# FrontEnd-signals.net
KiCad netlist of a schematic drawn in Altium Designer
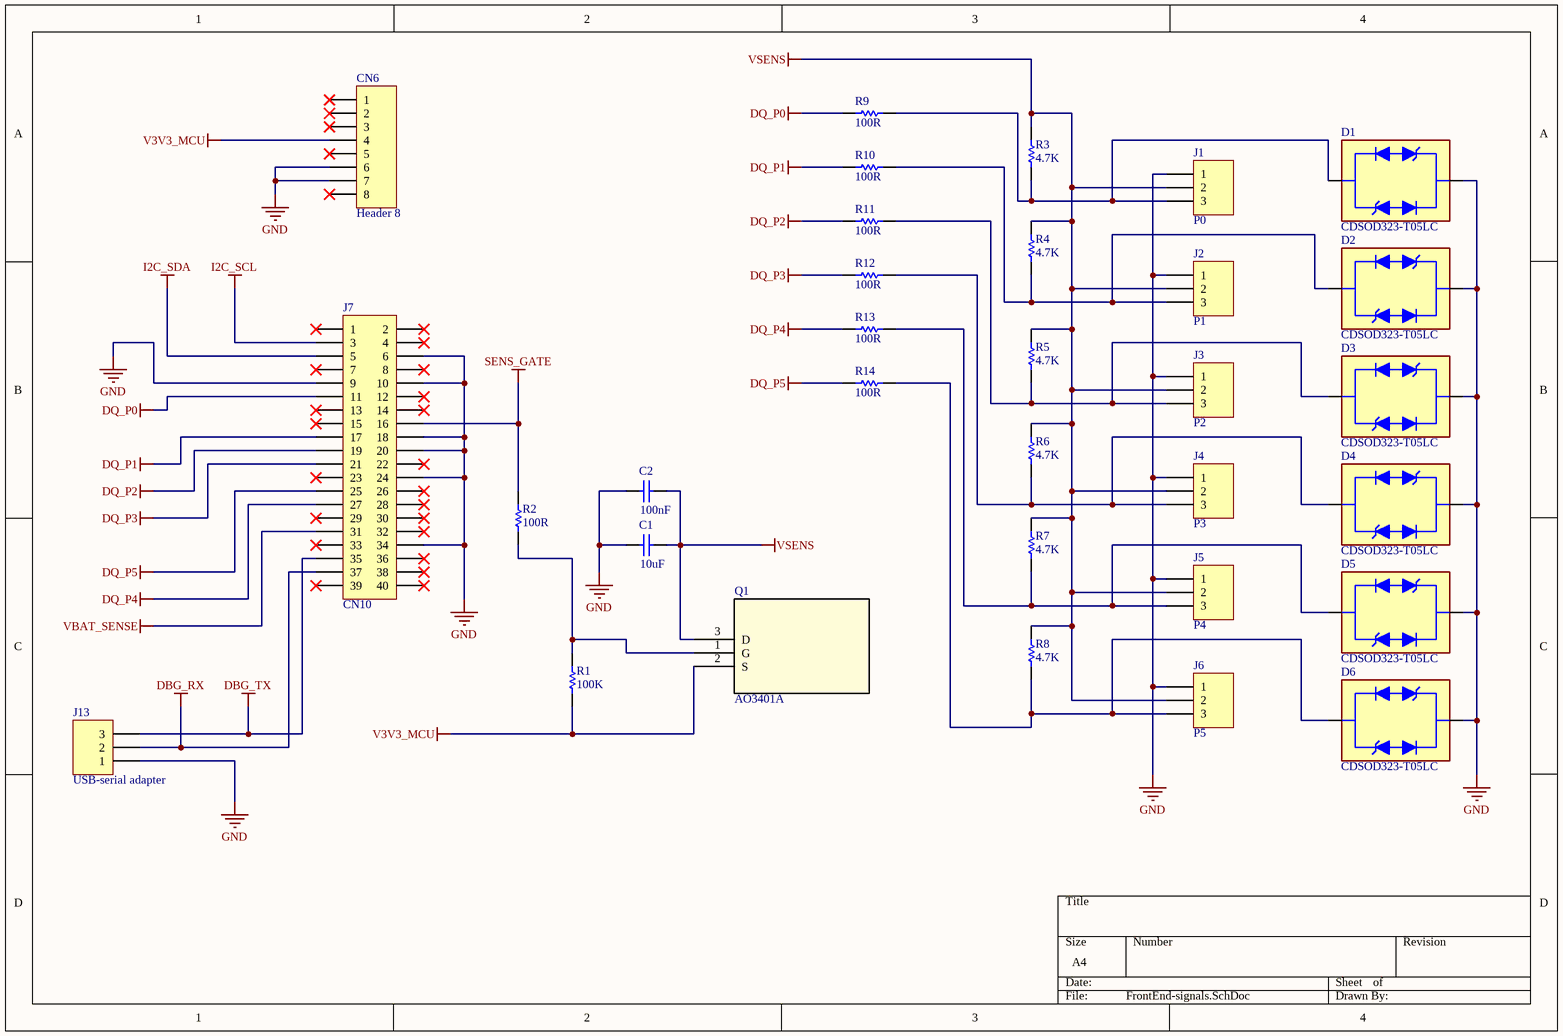
[diagram p0: FrontEnd-signals.SchDoc]

(export (version "E")
  (design (tool "Eeschema 10.0.6"))
  (components
    (comp (ref "C1")
      (value "10uF")
      (footprint "WaterTempNode_FE:CHIP0805-M")
      (description "Capacitor")
      (fields (field (name "Comment") "Cap") (field (name "PUBLISHER") "Altium Limited"))
      (libsource (lib "Miscellaneous Devices") (part "Cap"))
    )
    (comp (ref "C2")
      (value "100nF")
      (footprint "WaterTempNode_FE:CHIP0805-M")
      (description "Capacitor")
      (fields (field (name "Comment") "Cap") (field (name "PUBLISHER") "Altium Limited"))
      (libsource (lib "Miscellaneous Devices") (part "Cap"))
    )
    (comp (ref "CN6")
      (value "Header 8")
      (footprint "WaterTempNode_FE:HDR1X8-P254")
      (description "Header, 8-Pin")
      (fields (field (name "PUBLISHER") "Altium Limited"))
      (libsource (lib "Miscellaneous Connectors") (part "Header 8"))
    )
    (comp (ref "D1")
      (value "CDSOD323-T05LC")
      (footprint "CDSOD323_BRN-M")
      (description "A 05V, 350W, bi-directional, low capacitance, SOD323 pkg TVS Diode ¦ Bourns CDSOD323-T05LC")
      (fields (field (name "MF") "Bourns"))
      (libsource (lib "CDSOD323-T05LC") (part "CDSOD323-T05LC"))
    )
    (comp (ref "D2")
      (value "CDSOD323-T05LC")
      (footprint "CDSOD323_BRN-M")
      (description "A 05V, 350W, bi-directional, low capacitance, SOD323 pkg TVS Diode ¦ Bourns CDSOD323-T05LC")
      (fields (field (name "MF") "Bourns"))
      (libsource (lib "CDSOD323-T05LC") (part "CDSOD323-T05LC"))
    )
    (comp (ref "D3")
      (value "CDSOD323-T05LC")
      (footprint "CDSOD323_BRN-M")
      (description "A 05V, 350W, bi-directional, low capacitance, SOD323 pkg TVS Diode ¦ Bourns CDSOD323-T05LC")
      (fields (field (name "MF") "Bourns"))
      (libsource (lib "CDSOD323-T05LC") (part "CDSOD323-T05LC"))
    )
    (comp (ref "D4")
      (value "CDSOD323-T05LC")
      (footprint "CDSOD323_BRN-M")
      (description "A 05V, 350W, bi-directional, low capacitance, SOD323 pkg TVS Diode ¦ Bourns CDSOD323-T05LC")
      (fields (field (name "MF") "Bourns"))
      (libsource (lib "CDSOD323-T05LC") (part "CDSOD323-T05LC"))
    )
    (comp (ref "D5")
      (value "CDSOD323-T05LC")
      (footprint "CDSOD323_BRN-M")
      (description "A 05V, 350W, bi-directional, low capacitance, SOD323 pkg TVS Diode ¦ Bourns CDSOD323-T05LC")
      (fields (field (name "MF") "Bourns"))
      (libsource (lib "CDSOD323-T05LC") (part "CDSOD323-T05LC"))
    )
    (comp (ref "D6")
      (value "CDSOD323-T05LC")
      (footprint "CDSOD323_BRN-M")
      (description "A 05V, 350W, bi-directional, low capacitance, SOD323 pkg TVS Diode ¦ Bourns CDSOD323-T05LC")
      (fields (field (name "MF") "Bourns"))
      (libsource (lib "CDSOD323-T05LC") (part "CDSOD323-T05LC"))
    )
    (comp (ref "J1")
      (value "P0")
      (footprint "WaterTempNode_FE:PHX-MC15-3-G-35")
      (description "Header, 3-Pin")
      (fields (field (name "PUBLISHER") "Altium Limited"))
      (libsource (lib "") (part "Header 3_1"))
    )
    (comp (ref "J2")
      (value "P1")
      (footprint "WaterTempNode_FE:PHX-MC15-3-G-35")
      (description "Header, 3-Pin")
      (fields (field (name "PUBLISHER") "Altium Limited"))
      (libsource (lib "") (part "Header 3_1"))
    )
    (comp (ref "J3")
      (value "P2")
      (footprint "WaterTempNode_FE:PHX-MC15-3-G-35")
      (description "Header, 3-Pin")
      (fields (field (name "PUBLISHER") "Altium Limited"))
      (libsource (lib "") (part "Header 3_1"))
    )
    (comp (ref "J4")
      (value "P3")
      (footprint "WaterTempNode_FE:PHX-MC15-3-G-35")
      (description "Header, 3-Pin")
      (fields (field (name "PUBLISHER") "Altium Limited"))
      (libsource (lib "") (part "Header 3_1"))
    )
    (comp (ref "J5")
      (value "P4")
      (footprint "WaterTempNode_FE:PHX-MC15-3-G-35")
      (description "Header, 3-Pin")
      (fields (field (name "PUBLISHER") "Altium Limited"))
      (libsource (lib "") (part "Header 3_1"))
    )
    (comp (ref "J6")
      (value "P5")
      (footprint "WaterTempNode_FE:PHX-MC15-3-G-35")
      (description "Header, 3-Pin")
      (fields (field (name "PUBLISHER") "Altium Limited"))
      (libsource (lib "") (part "Header 3_1"))
    )
    (comp (ref "J7")
      (value "CN10")
      (footprint "WaterTempNode_FE:HDR2X20-BOX")
      (description "Header, 20-Pin, Dual row")
      (fields (field (name "PUBLISHER") "Altium Limited"))
      (libsource (lib "Miscellaneous Connectors") (part "Header 20X2"))
    )
    (comp (ref "J13")
      (value "USB-serial adapter")
      (footprint "WaterTempNode_FE:HDR1X3-P254")
      (description "Header, 3-Pin")
      (fields (field (name "PUBLISHER") "Altium Limited"))
      (libsource (lib "Miscellaneous Connectors") (part "Header 3"))
    )
    (comp (ref "Q1")
      (value "AO3401A")
      (footprint "SOT23-3-M")
      (description "Description")
      (fields (field (name "COPYRIGHT") "Copyright (C) 2026 Ultra Librarian. All rights reserved."))
      (libsource (lib "AO3401A") (part "AO3401A"))
    )
    (comp (ref "R1")
      (value "100K")
      (footprint "WaterTempNode_FE:CHIP0805-M")
      (description "Resistor")
      (fields (field (name "Comment") "pullup") (field (name "PUBLISHER") "Altium Limited"))
      (libsource (lib "Miscellaneous Devices") (part "Res1"))
    )
    (comp (ref "R2")
      (value "100R")
      (footprint "WaterTempNode_FE:CHIP0805-M")
      (description "Resistor")
      (fields (field (name "Comment") "pullup") (field (name "PUBLISHER") "Altium Limited"))
      (libsource (lib "Miscellaneous Devices") (part "Res1"))
    )
    (comp (ref "R3")
      (value "4.7K")
      (footprint "WaterTempNode_FE:CHIP0805-M")
      (description "Resistor")
      (fields (field (name "Comment") "pullup") (field (name "PUBLISHER") "Altium Limited"))
      (libsource (lib "Miscellaneous Devices") (part "Res1"))
    )
    (comp (ref "R4")
      (value "4.7K")
      (footprint "WaterTempNode_FE:CHIP0805-M")
      (description "Resistor")
      (fields (field (name "Comment") "pullup") (field (name "PUBLISHER") "Altium Limited"))
      (libsource (lib "Miscellaneous Devices") (part "Res1"))
    )
    (comp (ref "R5")
      (value "4.7K")
      (footprint "WaterTempNode_FE:CHIP0805-M")
      (description "Resistor")
      (fields (field (name "Comment") "pullup") (field (name "PUBLISHER") "Altium Limited"))
      (libsource (lib "Miscellaneous Devices") (part "Res1"))
    )
    (comp (ref "R6")
      (value "4.7K")
      (footprint "WaterTempNode_FE:CHIP0805-M")
      (description "Resistor")
      (fields (field (name "Comment") "pullup") (field (name "PUBLISHER") "Altium Limited"))
      (libsource (lib "Miscellaneous Devices") (part "Res1"))
    )
    (comp (ref "R7")
      (value "4.7K")
      (footprint "WaterTempNode_FE:CHIP0805-M")
      (description "Resistor")
      (fields (field (name "Comment") "pullup") (field (name "PUBLISHER") "Altium Limited"))
      (libsource (lib "Miscellaneous Devices") (part "Res1"))
    )
    (comp (ref "R8")
      (value "4.7K")
      (footprint "WaterTempNode_FE:CHIP0805-M")
      (description "Resistor")
      (fields (field (name "Comment") "pullup") (field (name "PUBLISHER") "Altium Limited"))
      (libsource (lib "Miscellaneous Devices") (part "Res1"))
    )
    (comp (ref "R9")
      (value "100R")
      (footprint "WaterTempNode_FE:CHIP0805-M")
      (description "Resistor")
      (fields (field (name "PUBLISHER") "Altium Limited"))
      (libsource (lib "Miscellaneous Devices") (part "Res1"))
    )
    (comp (ref "R10")
      (value "100R")
      (footprint "WaterTempNode_FE:CHIP0805-M")
      (description "Resistor")
      (fields (field (name "PUBLISHER") "Altium Limited"))
      (libsource (lib "Miscellaneous Devices") (part "Res1"))
    )
    (comp (ref "R11")
      (value "100R")
      (footprint "WaterTempNode_FE:CHIP0805-M")
      (description "Resistor")
      (fields (field (name "PUBLISHER") "Altium Limited"))
      (libsource (lib "Miscellaneous Devices") (part "Res1"))
    )
    (comp (ref "R12")
      (value "100R")
      (footprint "WaterTempNode_FE:CHIP0805-M")
      (description "Resistor")
      (fields (field (name "PUBLISHER") "Altium Limited"))
      (libsource (lib "Miscellaneous Devices") (part "Res1"))
    )
    (comp (ref "R13")
      (value "100R")
      (footprint "WaterTempNode_FE:CHIP0805-M")
      (description "Resistor")
      (fields (field (name "PUBLISHER") "Altium Limited"))
      (libsource (lib "Miscellaneous Devices") (part "Res1"))
    )
    (comp (ref "R14")
      (value "100R")
      (footprint "WaterTempNode_FE:CHIP0805-M")
      (description "Resistor")
      (fields (field (name "PUBLISHER") "Altium Limited"))
      (libsource (lib "Miscellaneous Devices") (part "Res1"))
    )
  )
  (nets
    (net (code "1") (name "DBG_RX") (class "Default")
      (node (ref "J13") (pin "2") (pinfunction "2_2") (pintype "passive"))
      (node (ref "J7") (pin "37") (pinfunction "37_37") (pintype "passive"))
    )
    (net (code "2") (name "DBG_TX") (class "Default")
      (node (ref "J13") (pin "3") (pinfunction "3_3") (pintype "passive"))
      (node (ref "J7") (pin "35") (pinfunction "35_35") (pintype "passive"))
    )
    (net (code "3") (name "DQ_P0") (class "Default")
      (node (ref "J7") (pin "11") (pinfunction "11_11") (pintype "passive"))
      (node (ref "R9") (pin "1") (pinfunction "1_1") (pintype "passive"))
    )
    (net (code "4") (name "DQ_P1") (class "Default")
      (node (ref "J7") (pin "17") (pinfunction "17_17") (pintype "passive"))
      (node (ref "R10") (pin "1") (pinfunction "1_1") (pintype "passive"))
    )
    (net (code "5") (name "DQ_P2") (class "Default")
      (node (ref "J7") (pin "19") (pinfunction "19_19") (pintype "passive"))
      (node (ref "R11") (pin "1") (pinfunction "1_1") (pintype "passive"))
    )
    (net (code "6") (name "DQ_P3") (class "Default")
      (node (ref "J7") (pin "21") (pinfunction "21_21") (pintype "passive"))
      (node (ref "R12") (pin "1") (pinfunction "1_1") (pintype "passive"))
    )
    (net (code "7") (name "DQ_P4") (class "Default")
      (node (ref "J7") (pin "27") (pinfunction "27_27") (pintype "passive"))
      (node (ref "R13") (pin "1") (pinfunction "1_1") (pintype "passive"))
    )
    (net (code "8") (name "DQ_P5") (class "Default")
      (node (ref "J7") (pin "25") (pinfunction "25_25") (pintype "passive"))
      (node (ref "R14") (pin "1") (pinfunction "1_1") (pintype "passive"))
    )
    (net (code "9") (name "GND") (class "Default")
      (node (ref "C1") (pin "1") (pinfunction "1_1") (pintype "passive"))
      (node (ref "C2") (pin "1") (pinfunction "1_1") (pintype "passive"))
      (node (ref "CN6") (pin "6") (pinfunction "6_6") (pintype "passive"))
      (node (ref "CN6") (pin "7") (pinfunction "7_7") (pintype "passive"))
      (node (ref "D1") (pin "2") (pinfunction "2_2") (pintype "passive"))
      (node (ref "D2") (pin "2") (pinfunction "2_2") (pintype "passive"))
      (node (ref "D3") (pin "2") (pinfunction "2_2") (pintype "passive"))
      (node (ref "D4") (pin "2") (pinfunction "2_2") (pintype "passive"))
      (node (ref "D5") (pin "2") (pinfunction "2_2") (pintype "passive"))
      (node (ref "D6") (pin "2") (pinfunction "2_2") (pintype "passive"))
      (node (ref "J1") (pin "1") (pinfunction "1_1") (pintype "passive"))
      (node (ref "J13") (pin "1") (pinfunction "1_1") (pintype "passive"))
      (node (ref "J2") (pin "1") (pinfunction "1_1") (pintype "passive"))
      (node (ref "J3") (pin "1") (pinfunction "1_1") (pintype "passive"))
      (node (ref "J4") (pin "1") (pinfunction "1_1") (pintype "passive"))
      (node (ref "J5") (pin "1") (pinfunction "1_1") (pintype "passive"))
      (node (ref "J6") (pin "1") (pinfunction "1_1") (pintype "passive"))
      (node (ref "J7") (pin "10") (pinfunction "10_10") (pintype "passive"))
      (node (ref "J7") (pin "18") (pinfunction "18_18") (pintype "passive"))
      (node (ref "J7") (pin "20") (pinfunction "20_20") (pintype "passive"))
      (node (ref "J7") (pin "24") (pinfunction "24_24") (pintype "passive"))
      (node (ref "J7") (pin "34") (pinfunction "34_34") (pintype "passive"))
      (node (ref "J7") (pin "6") (pinfunction "6_6") (pintype "passive"))
      (node (ref "J7") (pin "9") (pinfunction "9_9") (pintype "passive"))
    )
    (net (code "10") (name "I2C_SCL") (class "Default")
      (node (ref "J7") (pin "3") (pinfunction "3_3") (pintype "passive"))
    )
    (net (code "11") (name "I2C_SDA") (class "Default")
      (node (ref "J7") (pin "5") (pinfunction "5_5") (pintype "passive"))
    )
    (net (code "12") (name "Net-(D1-Pad1)") (class "Default")
      (node (ref "D1") (pin "1") (pinfunction "1_1") (pintype "passive"))
      (node (ref "J1") (pin "3") (pinfunction "3_3") (pintype "passive"))
      (node (ref "R3") (pin "2") (pinfunction "2_2") (pintype "passive"))
      (node (ref "R9") (pin "2") (pinfunction "2_2") (pintype "passive"))
    )
    (net (code "13") (name "Net-(D2-Pad1)") (class "Default")
      (node (ref "D2") (pin "1") (pinfunction "1_1") (pintype "passive"))
      (node (ref "J2") (pin "3") (pinfunction "3_3") (pintype "passive"))
      (node (ref "R10") (pin "2") (pinfunction "2_2") (pintype "passive"))
      (node (ref "R4") (pin "2") (pinfunction "2_2") (pintype "passive"))
    )
    (net (code "14") (name "Net-(D3-Pad1)") (class "Default")
      (node (ref "D3") (pin "1") (pinfunction "1_1") (pintype "passive"))
      (node (ref "J3") (pin "3") (pinfunction "3_3") (pintype "passive"))
      (node (ref "R11") (pin "2") (pinfunction "2_2") (pintype "passive"))
      (node (ref "R5") (pin "2") (pinfunction "2_2") (pintype "passive"))
    )
    (net (code "15") (name "Net-(D4-Pad1)") (class "Default")
      (node (ref "D4") (pin "1") (pinfunction "1_1") (pintype "passive"))
      (node (ref "J4") (pin "3") (pinfunction "3_3") (pintype "passive"))
      (node (ref "R12") (pin "2") (pinfunction "2_2") (pintype "passive"))
      (node (ref "R6") (pin "2") (pinfunction "2_2") (pintype "passive"))
    )
    (net (code "16") (name "Net-(D5-Pad1)") (class "Default")
      (node (ref "D5") (pin "1") (pinfunction "1_1") (pintype "passive"))
      (node (ref "J5") (pin "3") (pinfunction "3_3") (pintype "passive"))
      (node (ref "R13") (pin "2") (pinfunction "2_2") (pintype "passive"))
      (node (ref "R7") (pin "2") (pinfunction "2_2") (pintype "passive"))
    )
    (net (code "17") (name "Net-(D6-Pad1)") (class "Default")
      (node (ref "D6") (pin "1") (pinfunction "1_1") (pintype "passive"))
      (node (ref "J6") (pin "3") (pinfunction "3_3") (pintype "passive"))
      (node (ref "R14") (pin "2") (pinfunction "2_2") (pintype "passive"))
      (node (ref "R8") (pin "2") (pinfunction "2_2") (pintype "passive"))
    )
    (net (code "18") (name "Net-(Q1-G)") (class "Default")
      (node (ref "Q1") (pin "1") (pinfunction "G_1") (pintype "passive"))
      (node (ref "R1") (pin "1") (pinfunction "1_1") (pintype "passive"))
      (node (ref "R2") (pin "2") (pinfunction "2_2") (pintype "passive"))
    )
    (net (code "19") (name "SENS_GATE") (class "Default")
      (node (ref "J7") (pin "16") (pinfunction "16_16") (pintype "passive"))
      (node (ref "R2") (pin "1") (pinfunction "1_1") (pintype "passive"))
    )
    (net (code "20") (name "V3V3_MCU") (class "Default")
      (node (ref "CN6") (pin "4") (pinfunction "4_4") (pintype "passive"))
      (node (ref "Q1") (pin "2") (pinfunction "S_2") (pintype "passive"))
      (node (ref "R1") (pin "2") (pinfunction "2_2") (pintype "passive"))
    )
    (net (code "21") (name "VBAT_SENSE") (class "Default")
      (node (ref "J7") (pin "31") (pinfunction "31_31") (pintype "passive"))
    )
    (net (code "22") (name "VSENS") (class "Default")
      (node (ref "C1") (pin "2") (pinfunction "2_2") (pintype "passive"))
      (node (ref "C2") (pin "2") (pinfunction "2_2") (pintype "passive"))
      (node (ref "J1") (pin "2") (pinfunction "2_2") (pintype "passive"))
      (node (ref "J2") (pin "2") (pinfunction "2_2") (pintype "passive"))
      (node (ref "J3") (pin "2") (pinfunction "2_2") (pintype "passive"))
      (node (ref "J4") (pin "2") (pinfunction "2_2") (pintype "passive"))
      (node (ref "J5") (pin "2") (pinfunction "2_2") (pintype "passive"))
      (node (ref "J6") (pin "2") (pinfunction "2_2") (pintype "passive"))
      (node (ref "Q1") (pin "3") (pinfunction "D_3") (pintype "passive"))
      (node (ref "R3") (pin "1") (pinfunction "1_1") (pintype "passive"))
      (node (ref "R4") (pin "1") (pinfunction "1_1") (pintype "passive"))
      (node (ref "R5") (pin "1") (pinfunction "1_1") (pintype "passive"))
      (node (ref "R6") (pin "1") (pinfunction "1_1") (pintype "passive"))
      (node (ref "R7") (pin "1") (pinfunction "1_1") (pintype "passive"))
      (node (ref "R8") (pin "1") (pinfunction "1_1") (pintype "passive"))
    )
    (net (code "23") (name "unconnected-(CN6-Pad1)") (class "Default")
      (node (ref "CN6") (pin "1") (pinfunction "1_1") (pintype "passive+no_connect"))
    )
    (net (code "24") (name "unconnected-(CN6-Pad2)") (class "Default")
      (node (ref "CN6") (pin "2") (pinfunction "2_2") (pintype "passive+no_connect"))
    )
    (net (code "25") (name "unconnected-(CN6-Pad3)") (class "Default")
      (node (ref "CN6") (pin "3") (pinfunction "3_3") (pintype "passive+no_connect"))
    )
    (net (code "26") (name "unconnected-(CN6-Pad5)") (class "Default")
      (node (ref "CN6") (pin "5") (pinfunction "5_5") (pintype "passive+no_connect"))
    )
    (net (code "27") (name "unconnected-(CN6-Pad8)") (class "Default")
      (node (ref "CN6") (pin "8") (pinfunction "8_8") (pintype "passive+no_connect"))
    )
    (net (code "28") (name "unconnected-(J7-Pad1)") (class "Default")
      (node (ref "J7") (pin "1") (pinfunction "1_1") (pintype "passive+no_connect"))
    )
    (net (code "29") (name "unconnected-(J7-Pad2)") (class "Default")
      (node (ref "J7") (pin "2") (pinfunction "2_2") (pintype "passive+no_connect"))
    )
    (net (code "30") (name "unconnected-(J7-Pad4)") (class "Default")
      (node (ref "J7") (pin "4") (pinfunction "4_4") (pintype "passive+no_connect"))
    )
    (net (code "31") (name "unconnected-(J7-Pad7)") (class "Default")
      (node (ref "J7") (pin "7") (pinfunction "7_7") (pintype "passive+no_connect"))
    )
    (net (code "32") (name "unconnected-(J7-Pad8)") (class "Default")
      (node (ref "J7") (pin "8") (pinfunction "8_8") (pintype "passive+no_connect"))
    )
    (net (code "33") (name "unconnected-(J7-Pad12)") (class "Default")
      (node (ref "J7") (pin "12") (pinfunction "12_12") (pintype "passive+no_connect"))
    )
    (net (code "34") (name "unconnected-(J7-Pad13)") (class "Default")
      (node (ref "J7") (pin "13") (pinfunction "13_13") (pintype "passive+no_connect"))
    )
    (net (code "35") (name "unconnected-(J7-Pad14)") (class "Default")
      (node (ref "J7") (pin "14") (pinfunction "14_14") (pintype "passive+no_connect"))
    )
    (net (code "36") (name "unconnected-(J7-Pad15)") (class "Default")
      (node (ref "J7") (pin "15") (pinfunction "15_15") (pintype "passive+no_connect"))
    )
    (net (code "37") (name "unconnected-(J7-Pad22)") (class "Default")
      (node (ref "J7") (pin "22") (pinfunction "22_22") (pintype "passive+no_connect"))
    )
    (net (code "38") (name "unconnected-(J7-Pad23)") (class "Default")
      (node (ref "J7") (pin "23") (pinfunction "23_23") (pintype "passive+no_connect"))
    )
    (net (code "39") (name "unconnected-(J7-Pad26)") (class "Default")
      (node (ref "J7") (pin "26") (pinfunction "26_26") (pintype "passive+no_connect"))
    )
    (net (code "40") (name "unconnected-(J7-Pad28)") (class "Default")
      (node (ref "J7") (pin "28") (pinfunction "28_28") (pintype "passive+no_connect"))
    )
    (net (code "41") (name "unconnected-(J7-Pad29)") (class "Default")
      (node (ref "J7") (pin "29") (pinfunction "29_29") (pintype "passive+no_connect"))
    )
    (net (code "42") (name "unconnected-(J7-Pad30)") (class "Default")
      (node (ref "J7") (pin "30") (pinfunction "30_30") (pintype "passive+no_connect"))
    )
    (net (code "43") (name "unconnected-(J7-Pad32)") (class "Default")
      (node (ref "J7") (pin "32") (pinfunction "32_32") (pintype "passive+no_connect"))
    )
    (net (code "44") (name "unconnected-(J7-Pad33)") (class "Default")
      (node (ref "J7") (pin "33") (pinfunction "33_33") (pintype "passive+no_connect"))
    )
    (net (code "45") (name "unconnected-(J7-Pad36)") (class "Default")
      (node (ref "J7") (pin "36") (pinfunction "36_36") (pintype "passive+no_connect"))
    )
    (net (code "46") (name "unconnected-(J7-Pad38)") (class "Default")
      (node (ref "J7") (pin "38") (pinfunction "38_38") (pintype "passive+no_connect"))
    )
    (net (code "47") (name "unconnected-(J7-Pad39)") (class "Default")
      (node (ref "J7") (pin "39") (pinfunction "39_39") (pintype "passive+no_connect"))
    )
    (net (code "48") (name "unconnected-(J7-Pad40)") (class "Default")
      (node (ref "J7") (pin "40") (pinfunction "40_40") (pintype "passive+no_connect"))
    )
  )
)
